# LO.net
KiCad netlist of a schematic drawn in Altium Designer
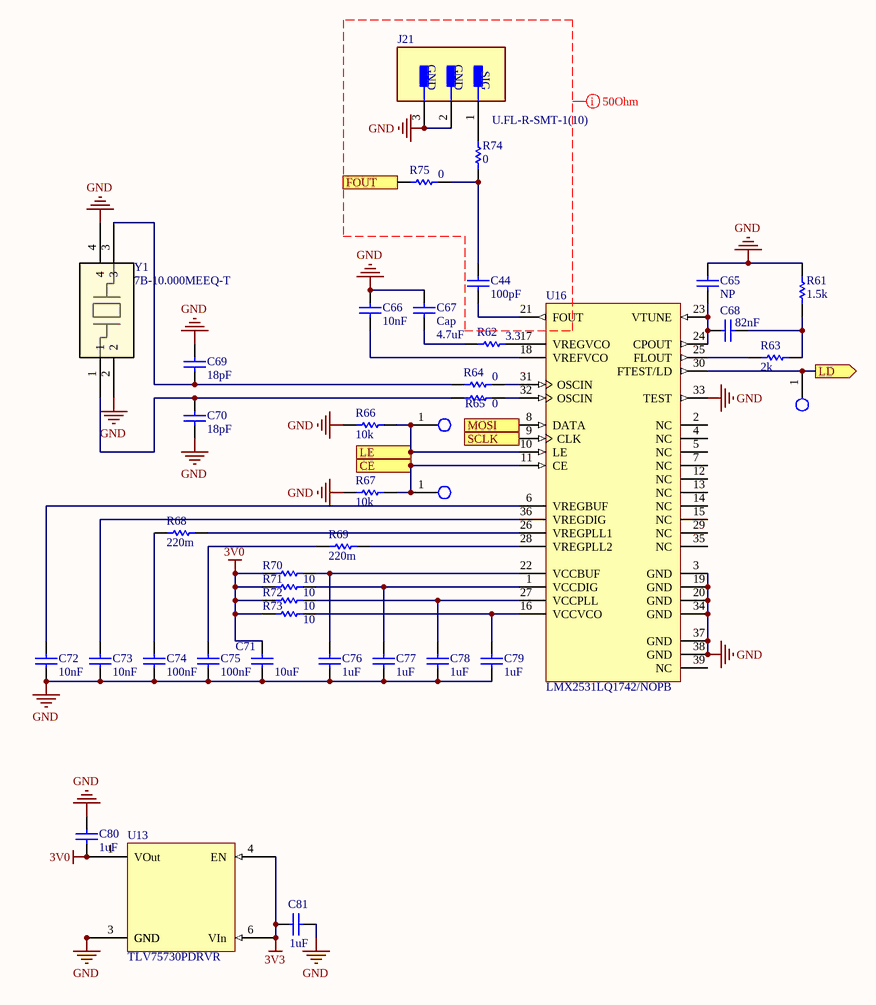
[diagram p0: LO.SchDoc]

(export (version "E")
  (design (tool "Eeschema 10.0.6"))
  (components
    (comp (ref "C44")
      (value "100pF")
      (footprint "0402-A")
      (description "Capacitor")
      (fields (field (name "Comment") "Cap") (field (name "PUBLISHER") "Altium Limited"))
      (libsource (lib "Miscellaneous Devices") (part "Cap"))
    )
    (comp (ref "C65")
      (value "NP")
      (footprint "0402-A")
      (description "Capacitor")
      (fields (field (name "Comment") "Cap") (field (name "PUBLISHER") "Altium Limited"))
      (libsource (lib "Miscellaneous Devices") (part "Cap"))
    )
    (comp (ref "C66")
      (value "10nF")
      (footprint "0402-A")
      (description "Capacitor")
      (fields (field (name "Comment") "Cap") (field (name "PUBLISHER") "Altium Limited"))
      (libsource (lib "Miscellaneous Devices") (part "Cap"))
    )
    (comp (ref "C67")
      (value "Cap")
      (footprint "6-0805_M")
      (description "Capacitor")
      (fields (field (name "ALTIUM_VALUE") "4.7uF") (field (name "PUBLISHER") "Altium Limited"))
      (libsource (lib "Miscellaneous Devices") (part "Cap"))
    )
    (comp (ref "C68")
      (value "82nF")
      (footprint "0402-A")
      (description "Capacitor")
      (fields (field (name "Comment") "Cap") (field (name "PUBLISHER") "Altium Limited"))
      (libsource (lib "Miscellaneous Devices") (part "Cap"))
    )
    (comp (ref "C69")
      (value "18pF")
      (footprint "0402-A")
      (description "Capacitor")
      (fields (field (name "Comment") "Cap") (field (name "PUBLISHER") "Altium Limited"))
      (libsource (lib "Miscellaneous Devices") (part "Cap"))
    )
    (comp (ref "C70")
      (value "18pF")
      (footprint "0402-A")
      (description "Capacitor")
      (fields (field (name "Comment") "Cap") (field (name "PUBLISHER") "Altium Limited"))
      (libsource (lib "Miscellaneous Devices") (part "Cap"))
    )
    (comp (ref "C71")
      (value "10uF")
      (footprint "C1206")
      (description "Capacitor")
      (fields (field (name "Comment") "Cap") (field (name "PUBLISHER") "Altium Limited"))
      (libsource (lib "Miscellaneous Devices") (part "Cap"))
    )
    (comp (ref "C72")
      (value "10nF")
      (footprint "0402-A")
      (description "Capacitor")
      (fields (field (name "Comment") "Cap") (field (name "PUBLISHER") "Altium Limited"))
      (libsource (lib "Miscellaneous Devices") (part "Cap"))
    )
    (comp (ref "C73")
      (value "10nF")
      (footprint "0402-A")
      (description "Capacitor")
      (fields (field (name "Comment") "Cap") (field (name "PUBLISHER") "Altium Limited"))
      (libsource (lib "Miscellaneous Devices") (part "Cap"))
    )
    (comp (ref "C74")
      (value "100nF")
      (footprint "0402-A")
      (description "Capacitor")
      (fields (field (name "Comment") "Cap") (field (name "PUBLISHER") "Altium Limited"))
      (libsource (lib "Miscellaneous Devices") (part "Cap"))
    )
    (comp (ref "C75")
      (value "100nF")
      (footprint "0402-A")
      (description "Capacitor")
      (fields (field (name "Comment") "Cap") (field (name "PUBLISHER") "Altium Limited"))
      (libsource (lib "Miscellaneous Devices") (part "Cap"))
    )
    (comp (ref "C76")
      (value "1uF")
      (footprint "1608[0603]")
      (description "Capacitor")
      (fields (field (name "Comment") "Cap") (field (name "PUBLISHER") "Altium Limited"))
      (libsource (lib "Miscellaneous Devices") (part "Cap"))
    )
    (comp (ref "C77")
      (value "1uF")
      (footprint "1608[0603]")
      (description "Capacitor")
      (fields (field (name "Comment") "Cap") (field (name "PUBLISHER") "Altium Limited"))
      (libsource (lib "Miscellaneous Devices") (part "Cap"))
    )
    (comp (ref "C78")
      (value "1uF")
      (footprint "1608[0603]")
      (description "Capacitor")
      (fields (field (name "Comment") "Cap") (field (name "PUBLISHER") "Altium Limited"))
      (libsource (lib "Miscellaneous Devices") (part "Cap"))
    )
    (comp (ref "C79")
      (value "1uF")
      (footprint "1608[0603]")
      (description "Capacitor")
      (fields (field (name "Comment") "Cap") (field (name "PUBLISHER") "Altium Limited"))
      (libsource (lib "Miscellaneous Devices") (part "Cap"))
    )
    (comp (ref "C80")
      (value "1uF")
      (footprint "1608[0603]")
      (description "Capacitor")
      (fields (field (name "Comment") "Cap") (field (name "PUBLISHER") "Altium Limited"))
      (libsource (lib "Miscellaneous Devices") (part "Cap"))
    )
    (comp (ref "C81")
      (value "1uF")
      (footprint "1608[0603]")
      (description "Capacitor")
      (fields (field (name "Comment") "Cap") (field (name "PUBLISHER") "Altium Limited"))
      (libsource (lib "Miscellaneous Devices") (part "Cap"))
    )
    (comp (ref "CLK5")
      (value "5029")
      (footprint "EXPOSED PAD 0.02X0.02")
      (libsource (lib "5029") (part "5029"))
    )
    (comp (ref "CLK6")
      (value "5029")
      (footprint "EXPOSED PAD 0.02X0.02")
      (libsource (lib "5029") (part "5029"))
    )
    (comp (ref "CLK7")
      (value "5029")
      (footprint "EXPOSED PAD 0.02X0.02")
      (libsource (lib "5029") (part "5029"))
    )
    (comp (ref "J21")
      (value "U.FL-R-SMT-1(10)")
      (footprint "FP-U_FL-R-SMT-1_10-MFG")
      (description "CONN U.FL RCPT STR 50 OHM SMD")
      (libsource (lib "Altium Content Vault") (part "eef6fde44c591823e8076210edfe12f"))
    )
    (comp (ref "R61")
      (value "1.5k")
      (footprint "0402-A")
      (description "Resistor")
      (fields (field (name "Comment") "Res1") (field (name "PUBLISHER") "Altium Limited"))
      (libsource (lib "Miscellaneous Devices") (part "Res1"))
    )
    (comp (ref "R62")
      (value "3.3")
      (footprint "0402-A")
      (description "Resistor")
      (fields (field (name "Comment") "Res1") (field (name "PUBLISHER") "Altium Limited"))
      (libsource (lib "Miscellaneous Devices") (part "Res1"))
    )
    (comp (ref "R63")
      (value "2k")
      (footprint "0402-A")
      (description "Resistor")
      (fields (field (name "Comment") "Res1") (field (name "PUBLISHER") "Altium Limited"))
      (libsource (lib "Miscellaneous Devices") (part "Res1"))
    )
    (comp (ref "R64")
      (value "0")
      (footprint "0402-A")
      (description "Resistor")
      (fields (field (name "Comment") "Res1") (field (name "PUBLISHER") "Altium Limited"))
      (libsource (lib "Miscellaneous Devices") (part "Res1"))
    )
    (comp (ref "R65")
      (value "0")
      (footprint "0402-A")
      (description "Resistor")
      (fields (field (name "Comment") "Res1") (field (name "PUBLISHER") "Altium Limited"))
      (libsource (lib "Miscellaneous Devices") (part "Res1"))
    )
    (comp (ref "R66")
      (value "10k")
      (footprint "0402-A")
      (description "Resistor")
      (fields (field (name "Comment") "Res1") (field (name "PUBLISHER") "Altium Limited"))
      (libsource (lib "Miscellaneous Devices") (part "Res1"))
    )
    (comp (ref "R67")
      (value "10k")
      (footprint "0402-A")
      (description "Resistor")
      (fields (field (name "Comment") "Res1") (field (name "PUBLISHER") "Altium Limited"))
      (libsource (lib "Miscellaneous Devices") (part "Res1"))
    )
    (comp (ref "R68")
      (value "220m")
      (footprint "0402-A")
      (description "Resistor")
      (fields (field (name "Comment") "Res1") (field (name "PUBLISHER") "Altium Limited"))
      (libsource (lib "Miscellaneous Devices") (part "Res1"))
    )
    (comp (ref "R69")
      (value "220m")
      (footprint "0402-A")
      (description "Resistor")
      (fields (field (name "Comment") "Res1") (field (name "PUBLISHER") "Altium Limited"))
      (libsource (lib "Miscellaneous Devices") (part "Res1"))
    )
    (comp (ref "R70")
      (value "10")
      (footprint "0402-A")
      (description "Resistor")
      (fields (field (name "Comment") "Res1") (field (name "PUBLISHER") "Altium Limited"))
      (libsource (lib "Miscellaneous Devices") (part "Res1"))
    )
    (comp (ref "R71")
      (value "10")
      (footprint "0402-A")
      (description "Resistor")
      (fields (field (name "Comment") "Res1") (field (name "PUBLISHER") "Altium Limited"))
      (libsource (lib "Miscellaneous Devices") (part "Res1"))
    )
    (comp (ref "R72")
      (value "10")
      (footprint "0402-A")
      (description "Resistor")
      (fields (field (name "Comment") "Res1") (field (name "PUBLISHER") "Altium Limited"))
      (libsource (lib "Miscellaneous Devices") (part "Res1"))
    )
    (comp (ref "R73")
      (value "10")
      (footprint "0402-A")
      (description "Resistor")
      (fields (field (name "Comment") "Res1") (field (name "PUBLISHER") "Altium Limited"))
      (libsource (lib "Miscellaneous Devices") (part "Res1"))
    )
    (comp (ref "R74")
      (value "0")
      (footprint "0402-A")
      (description "Resistor")
      (fields (field (name "Comment") "Res1") (field (name "PUBLISHER") "Altium Limited"))
      (libsource (lib "Miscellaneous Devices") (part "Res1"))
    )
    (comp (ref "R75")
      (value "0")
      (footprint "0402-A")
      (description "Resistor")
      (fields (field (name "Comment") "Res1") (field (name "PUBLISHER") "Altium Limited"))
      (libsource (lib "Miscellaneous Devices") (part "Res1"))
    )
    (comp (ref "U13")
      (value "TLV75730PDRVR")
      (footprint "TLV75730PDRVR")
      (libsource (lib "TLV75730PDRVR") (part "TLV75730PDRVR"))
    )
    (comp (ref "U16")
      (value "LMX2531LQ1742/NOPB")
      (footprint "NJG0036A_V")
      (description "High Performance Frequency Synthesizer System with Integrated VCO, 36-pin LLP, Pb-Free")
      (fields (field (name "MANUFACTURER") "Texas Instruments"))
      (libsource (lib "Altium Content Vault") (part "RF-FSYN-LMX2531LQ1500E"))
    )
    (comp (ref "Y1")
      (value "7B-10.000MEEQ-T")
      (footprint "CRYSTAL_TXC_7B")
      (description "No Description Available")
      (fields (field (name "COPYRIGHT") "Copyright (C) 2018 Accelerated Designs. All rights reserved"))
      (libsource (lib "7B-10.000MEEQ-T") (part "7B-10.000MEEQ-T"))
    )
  )
  (nets
    (net (code "1") (name "/CE") (class "Default")
      (node (ref "CLK7") (pin "1") (pintype "passive"))
      (node (ref "R67") (pin "2") (pinfunction "2_2") (pintype "passive"))
      (node (ref "U16") (pin "11") (pinfunction "CE_11") (pintype "input"))
    )
    (net (code "2") (name "/FOUT") (class "Default")
      (node (ref "R75") (pin "2") (pinfunction "2_2") (pintype "passive"))
    )
    (net (code "3") (name "/LD") (class "Default")
      (node (ref "CLK5") (pin "1") (pintype "passive"))
      (node (ref "U16") (pin "30") (pinfunction "FTEST/LD_30") (pintype "output"))
    )
    (net (code "4") (name "/LE") (class "Default")
      (node (ref "CLK6") (pin "1") (pintype "passive"))
      (node (ref "R66") (pin "2") (pinfunction "2_2") (pintype "passive"))
      (node (ref "U16") (pin "10") (pinfunction "LE_10") (pintype "input"))
    )
    (net (code "5") (name "/MOSI") (class "Default")
      (node (ref "U16") (pin "8") (pinfunction "DATA_8") (pintype "input"))
    )
    (net (code "6") (name "/SCLK") (class "Default")
      (node (ref "U16") (pin "9") (pinfunction "CLK_9") (pintype "input"))
    )
    (net (code "7") (name "3V0") (class "Default")
      (node (ref "C71") (pin "2") (pinfunction "2_2") (pintype "passive"))
      (node (ref "C80") (pin "2") (pinfunction "2_2") (pintype "passive"))
      (node (ref "R70") (pin "2") (pinfunction "2_2") (pintype "passive"))
      (node (ref "R71") (pin "2") (pinfunction "2_2") (pintype "passive"))
      (node (ref "R72") (pin "2") (pinfunction "2_2") (pintype "passive"))
      (node (ref "R73") (pin "2") (pinfunction "2_2") (pintype "passive"))
      (node (ref "U13") (pin "1") (pinfunction "VOut_1") (pintype "power_in"))
    )
    (net (code "8") (name "3V3") (class "Default")
      (node (ref "C81") (pin "2") (pinfunction "2_2") (pintype "passive"))
      (node (ref "U13") (pin "4") (pinfunction "EN_4") (pintype "input"))
      (node (ref "U13") (pin "6") (pinfunction "VIn_6") (pintype "input"))
    )
    (net (code "9") (name "GND") (class "Default")
      (node (ref "C65") (pin "1") (pinfunction "1_1") (pintype "passive"))
      (node (ref "C66") (pin "2") (pinfunction "2_2") (pintype "passive"))
      (node (ref "C67") (pin "2") (pinfunction "2_2") (pintype "passive"))
      (node (ref "C69") (pin "2") (pinfunction "2_2") (pintype "passive"))
      (node (ref "C70") (pin "1") (pinfunction "1_1") (pintype "passive"))
      (node (ref "C71") (pin "1") (pinfunction "1_1") (pintype "passive"))
      (node (ref "C72") (pin "1") (pinfunction "1_1") (pintype "passive"))
      (node (ref "C73") (pin "1") (pinfunction "1_1") (pintype "passive"))
      (node (ref "C74") (pin "1") (pinfunction "1_1") (pintype "passive"))
      (node (ref "C75") (pin "1") (pinfunction "1_1") (pintype "passive"))
      (node (ref "C76") (pin "2") (pinfunction "2_2") (pintype "passive"))
      (node (ref "C77") (pin "2") (pinfunction "2_2") (pintype "passive"))
      (node (ref "C78") (pin "2") (pinfunction "2_2") (pintype "passive"))
      (node (ref "C79") (pin "2") (pinfunction "2_2") (pintype "passive"))
      (node (ref "C80") (pin "1") (pinfunction "1_1") (pintype "passive"))
      (node (ref "C81") (pin "1") (pinfunction "1_1") (pintype "passive"))
      (node (ref "J21") (pin "2") (pinfunction "GND_2") (pintype "power_in"))
      (node (ref "J21") (pin "3") (pinfunction "GND_3") (pintype "power_in"))
      (node (ref "R61") (pin "1") (pinfunction "1_1") (pintype "passive"))
      (node (ref "R66") (pin "1") (pinfunction "1_1") (pintype "passive"))
      (node (ref "R67") (pin "1") (pinfunction "1_1") (pintype "passive"))
      (node (ref "U13") (pin "3") (pinfunction "GND_3") (pintype "power_in"))
      (node (ref "U13") (pin "7") (pinfunction "GND_7") (pintype "power_in"))
      (node (ref "U16") (pin "19") (pinfunction "GND_19") (pintype "power_in"))
      (node (ref "U16") (pin "20") (pinfunction "GND_20") (pintype "power_in"))
      (node (ref "U16") (pin "3") (pinfunction "GND_3") (pintype "power_in"))
      (node (ref "U16") (pin "33") (pinfunction "TEST_33") (pintype "output"))
      (node (ref "U16") (pin "34") (pinfunction "GND_34") (pintype "power_in"))
      (node (ref "U16") (pin "37") (pinfunction "GND_37") (pintype "power_in"))
      (node (ref "U16") (pin "38") (pinfunction "GND_38") (pintype "power_in"))
      (node (ref "Y1") (pin "2") (pinfunction "2_2") (pintype "passive"))
      (node (ref "Y1") (pin "4") (pinfunction "4_4") (pintype "passive"))
    )
    (net (code "10") (name "Net-(C44-Pad1)") (class "Default")
      (node (ref "C44") (pin "1") (pinfunction "1_1") (pintype "passive"))
      (node (ref "R74") (pin "2") (pinfunction "2_2") (pintype "passive"))
      (node (ref "R75") (pin "1") (pinfunction "1_1") (pintype "passive"))
    )
    (net (code "11") (name "Net-(C67-Pad1)") (class "Default")
      (node (ref "C67") (pin "1") (pinfunction "1_1") (pintype "passive"))
      (node (ref "R62") (pin "2") (pinfunction "2_2") (pintype "passive"))
    )
    (net (code "12") (name "Net-(C68-Pad1)") (class "Default")
      (node (ref "C68") (pin "1") (pinfunction "1_1") (pintype "passive"))
      (node (ref "R61") (pin "2") (pinfunction "2_2") (pintype "passive"))
      (node (ref "R63") (pin "2") (pinfunction "2_2") (pintype "passive"))
    )
    (net (code "13") (name "Net-(C69-Pad1)") (class "Default")
      (node (ref "C69") (pin "1") (pinfunction "1_1") (pintype "passive"))
      (node (ref "R64") (pin "2") (pinfunction "2_2") (pintype "passive"))
      (node (ref "Y1") (pin "3") (pinfunction "3_3") (pintype "passive"))
    )
    (net (code "14") (name "Net-(C70-Pad2)") (class "Default")
      (node (ref "C70") (pin "2") (pinfunction "2_2") (pintype "passive"))
      (node (ref "R65") (pin "2") (pinfunction "2_2") (pintype "passive"))
      (node (ref "Y1") (pin "1") (pinfunction "1_1") (pintype "passive"))
    )
    (net (code "15") (name "Net-(C74-Pad2)") (class "Default")
      (node (ref "C74") (pin "2") (pinfunction "2_2") (pintype "passive"))
      (node (ref "R68") (pin "2") (pinfunction "2_2") (pintype "passive"))
    )
    (net (code "16") (name "Net-(C75-Pad2)") (class "Default")
      (node (ref "C75") (pin "2") (pinfunction "2_2") (pintype "passive"))
      (node (ref "R69") (pin "2") (pinfunction "2_2") (pintype "passive"))
    )
    (net (code "17") (name "Net-(J21-SIG)") (class "Default")
      (node (ref "J21") (pin "1") (pinfunction "SIG_1") (pintype "passive"))
      (node (ref "R74") (pin "1") (pinfunction "1_1") (pintype "passive"))
    )
    (net (code "18") (name "Net-(R64-Pad1)") (class "Default")
      (node (ref "R64") (pin "1") (pinfunction "1_1") (pintype "passive"))
      (node (ref "U16") (pin "31") (pinfunction "OSCIN_31") (pintype "input"))
    )
    (net (code "19") (name "Net-(R65-Pad1)") (class "Default")
      (node (ref "R65") (pin "1") (pinfunction "1_1") (pintype "passive"))
      (node (ref "U16") (pin "32") (pinfunction "OSCIN_32") (pintype "input"))
    )
    (net (code "20") (name "Net-(U16-CPOUT)") (class "Default")
      (node (ref "C65") (pin "2") (pinfunction "2_2") (pintype "passive"))
      (node (ref "C68") (pin "2") (pinfunction "2_2") (pintype "passive"))
      (node (ref "U16") (pin "23") (pinfunction "VTUNE_23") (pintype "input"))
      (node (ref "U16") (pin "24") (pinfunction "CPOUT_24") (pintype "output"))
    )
    (net (code "21") (name "Net-(U16-FLOUT)") (class "Default")
      (node (ref "R63") (pin "1") (pinfunction "1_1") (pintype "passive"))
      (node (ref "U16") (pin "25") (pinfunction "FLOUT_25") (pintype "output"))
    )
    (net (code "22") (name "Net-(U16-FOUT)") (class "Default")
      (node (ref "C44") (pin "2") (pinfunction "2_2") (pintype "passive"))
      (node (ref "U16") (pin "21") (pinfunction "FOUT_21") (pintype "output"))
    )
    (net (code "23") (name "Net-(U16-VCCBUF)") (class "Default")
      (node (ref "C76") (pin "1") (pinfunction "1_1") (pintype "passive"))
      (node (ref "R70") (pin "1") (pinfunction "1_1") (pintype "passive"))
      (node (ref "U16") (pin "22") (pinfunction "VCCBUF_22") (pintype "power_in"))
    )
    (net (code "24") (name "Net-(U16-VCCDIG)") (class "Default")
      (node (ref "C77") (pin "1") (pinfunction "1_1") (pintype "passive"))
      (node (ref "R71") (pin "1") (pinfunction "1_1") (pintype "passive"))
      (node (ref "U16") (pin "1") (pinfunction "VCCDIG_1") (pintype "power_in"))
    )
    (net (code "25") (name "Net-(U16-VCCPLL)") (class "Default")
      (node (ref "C78") (pin "1") (pinfunction "1_1") (pintype "passive"))
      (node (ref "R72") (pin "1") (pinfunction "1_1") (pintype "passive"))
      (node (ref "U16") (pin "27") (pinfunction "VCCPLL_27") (pintype "power_in"))
    )
    (net (code "26") (name "Net-(U16-VCCVCO)") (class "Default")
      (node (ref "C79") (pin "1") (pinfunction "1_1") (pintype "passive"))
      (node (ref "R73") (pin "1") (pinfunction "1_1") (pintype "passive"))
      (node (ref "U16") (pin "16") (pinfunction "VCCVCO_16") (pintype "power_in"))
    )
    (net (code "27") (name "Net-(U16-VREFVCO)") (class "Default")
      (node (ref "C66") (pin "1") (pinfunction "1_1") (pintype "passive"))
      (node (ref "U16") (pin "18") (pinfunction "VREFVCO_18") (pintype "power_in"))
    )
    (net (code "28") (name "Net-(U16-VREGBUF)") (class "Default")
      (node (ref "C72") (pin "2") (pinfunction "2_2") (pintype "passive"))
      (node (ref "U16") (pin "6") (pinfunction "VREGBUF_6") (pintype "power_in"))
    )
    (net (code "29") (name "Net-(U16-VREGDIG)") (class "Default")
      (node (ref "C73") (pin "2") (pinfunction "2_2") (pintype "passive"))
      (node (ref "U16") (pin "36") (pinfunction "VREGDIG_36") (pintype "power_in"))
    )
    (net (code "30") (name "Net-(U16-VREGPLL1)") (class "Default")
      (node (ref "R68") (pin "1") (pinfunction "1_1") (pintype "passive"))
      (node (ref "U16") (pin "26") (pinfunction "VREGPLL1_26") (pintype "power_in"))
    )
    (net (code "31") (name "Net-(U16-VREGPLL2)") (class "Default")
      (node (ref "R69") (pin "1") (pinfunction "1_1") (pintype "passive"))
      (node (ref "U16") (pin "28") (pinfunction "VREGPLL2_28") (pintype "power_in"))
    )
    (net (code "32") (name "Net-(U16-VREGVCO)") (class "Default")
      (node (ref "R62") (pin "1") (pinfunction "1_1") (pintype "passive"))
      (node (ref "U16") (pin "17") (pinfunction "VREGVCO_17") (pintype "power_in"))
    )
    (net (code "33") (name "unconnected-(U16-NC-Pad2)") (class "Default")
      (node (ref "U16") (pin "2") (pinfunction "NC_2") (pintype "passive"))
    )
    (net (code "34") (name "unconnected-(U16-NC-Pad4)") (class "Default")
      (node (ref "U16") (pin "4") (pinfunction "NC_4") (pintype "passive"))
    )
    (net (code "35") (name "unconnected-(U16-NC-Pad5)") (class "Default")
      (node (ref "U16") (pin "5") (pinfunction "NC_5") (pintype "passive"))
    )
    (net (code "36") (name "unconnected-(U16-NC-Pad7)") (class "Default")
      (node (ref "U16") (pin "7") (pinfunction "NC_7") (pintype "passive"))
    )
    (net (code "37") (name "unconnected-(U16-NC-Pad12)") (class "Default")
      (node (ref "U16") (pin "12") (pinfunction "NC_12") (pintype "passive"))
    )
    (net (code "38") (name "unconnected-(U16-NC-Pad13)") (class "Default")
      (node (ref "U16") (pin "13") (pinfunction "NC_13") (pintype "passive"))
    )
    (net (code "39") (name "unconnected-(U16-NC-Pad14)") (class "Default")
      (node (ref "U16") (pin "14") (pinfunction "NC_14") (pintype "passive"))
    )
    (net (code "40") (name "unconnected-(U16-NC-Pad15)") (class "Default")
      (node (ref "U16") (pin "15") (pinfunction "NC_15") (pintype "passive"))
    )
    (net (code "41") (name "unconnected-(U16-NC-Pad29)") (class "Default")
      (node (ref "U16") (pin "29") (pinfunction "NC_29") (pintype "passive"))
    )
    (net (code "42") (name "unconnected-(U16-NC-Pad35)") (class "Default")
      (node (ref "U16") (pin "35") (pinfunction "NC_35") (pintype "passive"))
    )
    (net (code "43") (name "unconnected-(U16-NC-Pad39)") (class "Default")
      (node (ref "U16") (pin "39") (pinfunction "NC_39") (pintype "passive"))
    )
  )
)
